# Sheet1.net
KiCad netlist of a schematic drawn in Altium Designer
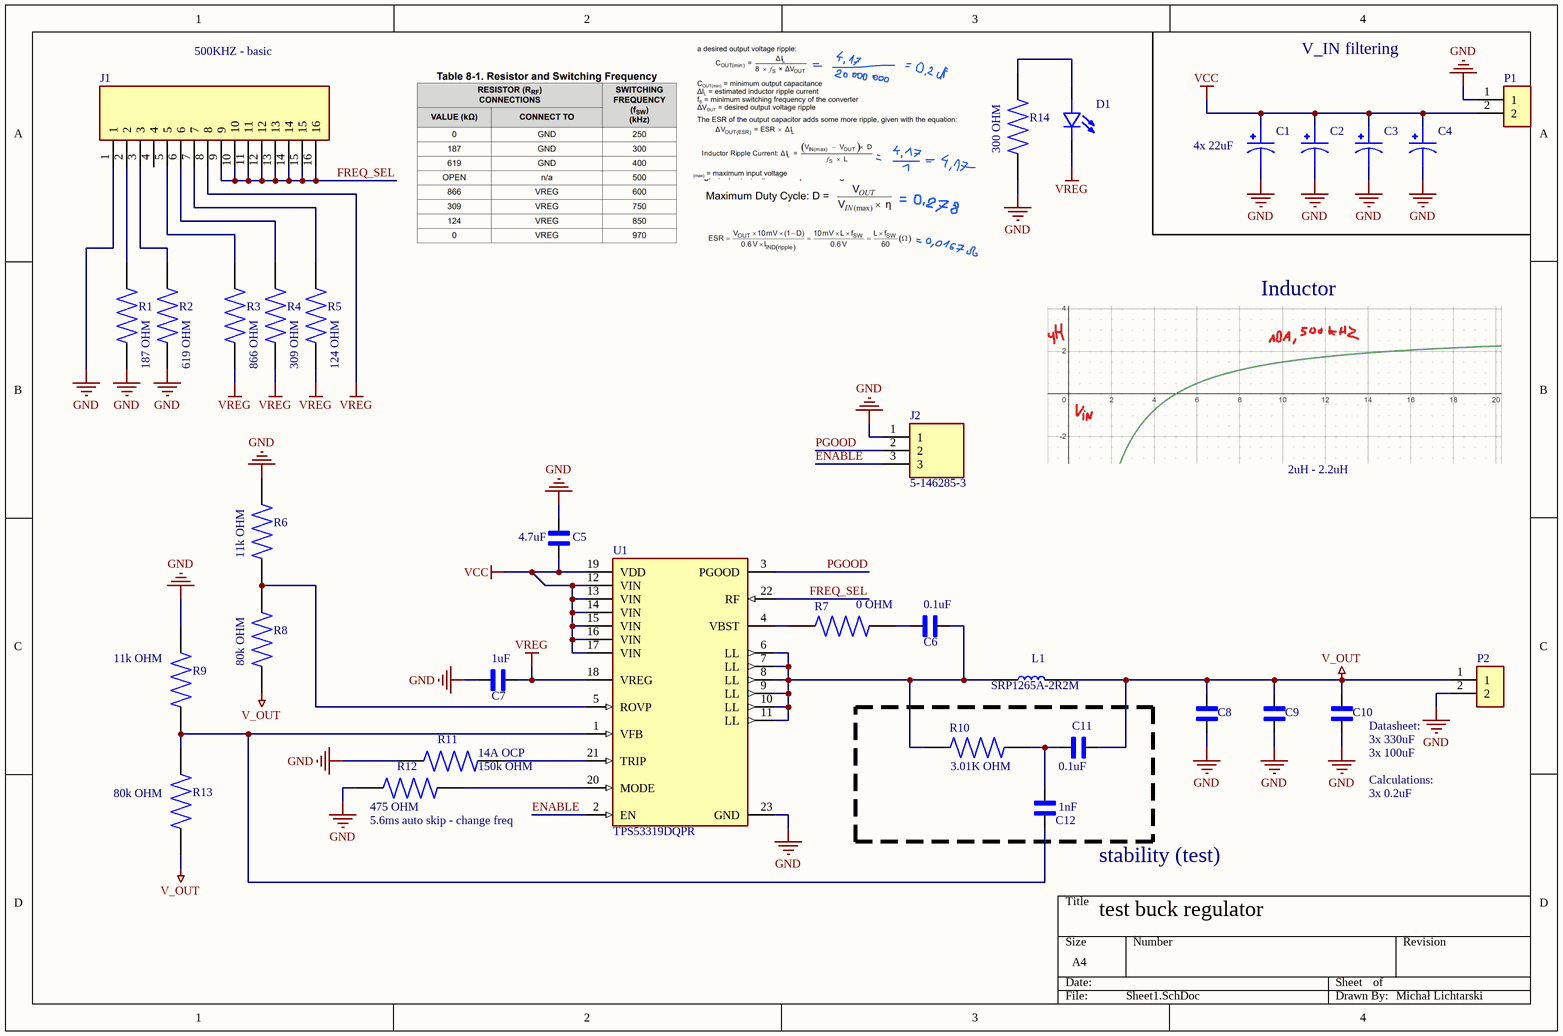
[diagram p0: Sheet1.SchDoc]

(export (version "E")
  (design (tool "Eeschema 10.0.6"))
  (components
    (comp (ref "C1")
      (value "TCJD226M035R0070")
      (footprint "TPSD107M016S0100:CAPPM7343X310N")
      (description "CAP TANT POLY 22UF 35V 2917")
      (fields (field (name "MF") "{'manufacturer': u'AVX'}") (field (name "MP") "TPSD107M016S0100"))
      (libsource (lib "*") (part "TPSD107M016S0100"))
    )
    (comp (ref "C2")
      (value "TCJD226M035R0070")
      (footprint "TPSD107M016S0100:CAPPM7343X310N")
      (description "CAP TANT POLY 22UF 35V 2917")
      (fields (field (name "MF") "{'manufacturer': u'AVX'}") (field (name "MP") "TPSD107M016S0100"))
      (libsource (lib "*") (part "TPSD107M016S0100"))
    )
    (comp (ref "C3")
      (value "TCJD226M035R0070")
      (footprint "TPSD107M016S0100:CAPPM7343X310N")
      (description "CAP TANT POLY 22UF 35V 2917")
      (fields (field (name "MF") "{'manufacturer': u'AVX'}") (field (name "MP") "TPSD107M016S0100"))
      (libsource (lib "*") (part "TPSD107M016S0100"))
    )
    (comp (ref "C4")
      (value "TCJD226M035R0070")
      (footprint "TPSD107M016S0100:CAPPM7343X310N")
      (description "CAP TANT POLY 22UF 35V 2917")
      (fields (field (name "MF") "{'manufacturer': u'AVX'}") (field (name "MP") "TPSD107M016S0100"))
      (libsource (lib "*") (part "TPSD107M016S0100"))
    )
    (comp (ref "C5")
      (value "CL21A475KLCLQNC")
      (footprint "CL21A475KLCLQNC:CAPC2012X135N")
      (description "MLCC 0805 X5R 4.7uF Â±10% 35V T:0.85mm")
      (fields (field (name "MF") "{'manufacturer': u'Samsung'}"))
      (libsource (lib "*") (part "CL21A475KLCLQNC"))
    )
    (comp (ref "C6")
      (value "CL10B104KB8NNNC")
      (footprint "CL10B104KB8NNNC:CAPC1608X90N")
      (fields (field (name "MF") "{'manufacturer': u'Samsung Electro-Mechanics'}"))
      (libsource (lib "*") (part "CL10B104KB8NNNC"))
    )
    (comp (ref "C7")
      (value "CL21B105KBFNNNE")
      (footprint "CL21B105KBFNNNE:CAPC2012X140N")
      (description "Capacitor: ceramic; MLCC; 1uF; 50V; X7R; Â±10%; SMD; 0805")
      (fields (field (name "MF") "{'manufacturer': u'Samsung Electro-Mechanics'}"))
      (libsource (lib "*") (part "CL21B105KBFNNNE"))
    )
    (comp (ref "C8")
      (value "CL32A107MPVNNNE")
      (footprint "CL32A107MPVNNNE:ANTC3225X280N")
      (description "Cap Ceramic 100uF 10V X5R 20% SMD 1210 85Â°C Embossed T/R")
      (fields (field (name "MF") "{'manufacturer': u'Samsung Electro-Mechanics'}"))
      (libsource (lib "*") (part "CL32A107MPVNNNE"))
    )
    (comp (ref "C9")
      (value "CL32A107MPVNNNE")
      (footprint "CL32A107MPVNNNE:ANTC3225X280N")
      (description "Cap Ceramic 100uF 10V X5R 20% SMD 1210 85Â°C Embossed T/R")
      (fields (field (name "MF") "{'manufacturer': u'Samsung Electro-Mechanics'}"))
      (libsource (lib "*") (part "CL32A107MPVNNNE"))
    )
    (comp (ref "C10")
      (value "CL32A107MPVNNNE")
      (footprint "CL32A107MPVNNNE:ANTC3225X280N")
      (description "Cap Ceramic 100uF 10V X5R 20% SMD 1210 85Â°C Embossed T/R")
      (fields (field (name "MF") "{'manufacturer': u'Samsung Electro-Mechanics'}"))
      (libsource (lib "*") (part "CL32A107MPVNNNE"))
    )
    (comp (ref "C11")
      (value "CL10B104KB8NNNC")
      (footprint "CL10B104KB8NNNC:CAPC1608X90N")
      (fields (field (name "MF") "{'manufacturer': u'Samsung Electro-Mechanics'}"))
      (libsource (lib "*") (part "CL10B104KB8NNNC"))
    )
    (comp (ref "C12")
      (value "CL10C102JB8NNNC")
      (footprint "CL10B104KB8NNNC:CAPC1608X90N")
      (description "CAP CER 1000PF 50V C0G/NP0 0603")
      (fields
        (field (name "MF") "{'manufacturer': u'Samsung Electro-Mechanics'}")
        (field (name "MP") "CL10B104KB8NNNC")
      )
      (libsource (lib "") (part "CL10B104KB8NNNC_1"))
    )
    (comp (ref "D1")
      (value "LTST-C190GKT")
      (footprint "LTST-C190GKT:LEDC1608X35N")
      (fields (field (name "MF") "{'manufacturer': u'Lite-On Inc.'}"))
      (libsource (lib "*") (part "LTST-C190GKT"))
    )
    (comp (ref "J1")
      (value "87227-8")
      (footprint "87227-8:TE_87227-8")
      (fields (field (name "MF") "{'manufacturer': u'TE Connectivity'}"))
      (libsource (lib "*") (part "87227-8"))
    )
    (comp (ref "J2")
      (value "5-146285-3")
      (footprint "TE_5-146285-3")
      (fields (field (name "MF") "{'manufacturer': u'TE Connectivity'}"))
      (libsource (lib "5-146285-3") (part "5-146285-3"))
    )
    (comp (ref "L1")
      (value "SRP1265A-2R2M")
      (footprint "SRP1265A-330M:IND_SRP1265A-330M")
      (description "Inductor Power Shielded Wirewound 33uH 20% 100KHz Carbonyl Powder 8A 58mOhm DCR Automotive T/R")
      (fields (field (name "MF") "{'manufacturer': u'Bourns'}") (field (name "MP") "SRP1265A-330M"))
      (libsource (lib "*") (part "SRP1265A-330M"))
    )
    (comp (ref "P1")
      (value "282837-2")
      (footprint "282837-2:TE_282837-2")
      (description "TERM BLOCK 5.08MM 2POS SIDE ENTY")
      (fields (field (name "MF") "{'manufacturer': u'TE Connectivity'}"))
      (libsource (lib "*") (part "282837-2"))
    )
    (comp (ref "P2")
      (value "282837-2")
      (footprint "282837-2:TE_282837-2")
      (description "TERM BLOCK 5.08MM 2POS SIDE ENTY")
      (fields (field (name "MF") "{'manufacturer': u'TE Connectivity'}"))
      (libsource (lib "*") (part "282837-2"))
    )
    (comp (ref "R1")
      (value "RC0603FR-07187RL")
      (footprint "ERJ-3EKF4750V:RES_ERJ3EKF4750V")
      (description "RES 187 OHM 1% 1/10W 0603")
      (fields (field (name "MF") "{'manufacturer': u'Panasonic'}") (field (name "MP") "ERJ3EKF4750V"))
      (libsource (lib "*") (part "ERJ3EKF4750V"))
    )
    (comp (ref "R2")
      (value "RC0603FR-07619RL")
      (footprint "ERJ-3EKF4750V:RES_ERJ3EKF4750V")
      (description "RES 619 OHM 1% 1/10W 0603")
      (fields (field (name "MF") "{'manufacturer': u'Panasonic'}") (field (name "MP") "ERJ3EKF4750V"))
      (libsource (lib "*") (part "ERJ3EKF4750V"))
    )
    (comp (ref "R3")
      (value "RC0603FR-07866RL")
      (footprint "ERJ-3EKF4750V:RES_ERJ3EKF4750V")
      (description "RES 866 OHM 1% 1/10W 0603")
      (fields (field (name "MF") "{'manufacturer': u'Panasonic'}") (field (name "MP") "ERJ3EKF4750V"))
      (libsource (lib "*") (part "ERJ3EKF4750V"))
    )
    (comp (ref "R4")
      (value "RC0603FR-07309RL")
      (footprint "ERJ-3EKF4750V:RES_ERJ3EKF4750V")
      (description "RES 309 OHM 1% 1/10W 0603")
      (fields (field (name "MF") "{'manufacturer': u'Panasonic'}") (field (name "MP") "ERJ3EKF4750V"))
      (libsource (lib "*") (part "ERJ3EKF4750V"))
    )
    (comp (ref "R5")
      (value "ERJ-3EKF1240V")
      (footprint "ERJ-3EKF4750V:RES_ERJ3EKF4750V")
      (description "RES SMD 124 OHM 1% 1/10W 0603")
      (fields (field (name "MF") "{'manufacturer': u'Panasonic'}") (field (name "MP") "ERJ3EKF4750V"))
      (libsource (lib "*") (part "ERJ3EKF4750V"))
    )
    (comp (ref "R6")
      (value "ERJ-PB3D1102V")
      (footprint "ERJ-3EKF4750V:RES_ERJ3EKF4750V")
      (description "RES SMD 11K OHM 0.5% 1/5W 0603")
      (fields (field (name "MF") "{'manufacturer': u'Panasonic'}") (field (name "MP") "ERJ3EKF4750V"))
      (libsource (lib "*") (part "ERJ3EKF4750V"))
    )
    (comp (ref "R7")
      (value "ERJ-3GEY0R00V")
      (footprint "ERJ-3GEY0R00V:RES_ERJ-3GEY0R00V")
      (fields (field (name "MF") "{'manufacturer': u'Panasonic'}"))
      (libsource (lib "*") (part "ERJ-3GEY0R00V"))
    )
    (comp (ref "R8")
      (value "RC0603FR-0780K6L")
      (footprint "ERJ-3EKF4750V:RES_ERJ3EKF4750V")
      (description "RES 80.6K OHM 1% 1/10W 0603")
      (fields (field (name "MF") "{'manufacturer': u'Panasonic'}") (field (name "MP") "ERJ3EKF4750V"))
      (libsource (lib "*") (part "ERJ3EKF4750V"))
    )
    (comp (ref "R9")
      (value "ERJ-PB3D1102V")
      (footprint "ERJ-3EKF4750V:RES_ERJ3EKF4750V")
      (description "RES SMD 11K OHM 0.5% 1/5W 0603")
      (fields (field (name "MF") "{'manufacturer': u'Panasonic'}") (field (name "MP") "ERJ3EKF4750V"))
      (libsource (lib "*") (part "ERJ3EKF4750V"))
    )
    (comp (ref "R10")
      (value "ERJ-3EKF3011V")
      (footprint "ERJ-3GEY0R00V:RES_ERJ-3GEY0R00V")
      (description "RES SMD 3.01K OHM 1% 1/10W 0603")
      (fields (field (name "MF") "{'manufacturer': u'Panasonic'}") (field (name "MP") "ERJ-3GEY0R00V"))
      (libsource (lib "*") (part "ERJ-3GEY0R00V"))
    )
    (comp (ref "R11")
      (value "RC0603FR-07150KL")
      (footprint "ERJ-3EKF4750V:RES_ERJ3EKF4750V")
      (description "RES 150K OHM 1% 1/10W 0603")
      (fields (field (name "MF") "{'manufacturer': u'Panasonic'}") (field (name "MP") "ERJ3EKF4750V"))
      (libsource (lib "*") (part "ERJ3EKF4750V"))
    )
    (comp (ref "R12")
      (value "ERJ-3EKF4750V")
      (footprint "ERJ-3EKF4750V:RES_ERJ3EKF4750V")
      (description "RES SMD 475 OHM 1% 1/10W 0603")
      (fields (field (name "MF") "{'manufacturer': u'Panasonic'}") (field (name "MP") "ERJ3EKF4750V"))
      (libsource (lib "*") (part "ERJ3EKF4750V"))
    )
    (comp (ref "R13")
      (value "RC0603FR-0780K6L")
      (footprint "ERJ-3EKF4750V:RES_ERJ3EKF4750V")
      (description "RES 80.6K OHM 1% 1/10W 0603")
      (fields (field (name "MF") "{'manufacturer': u'Panasonic'}") (field (name "MP") "ERJ3EKF4750V"))
      (libsource (lib "*") (part "ERJ3EKF4750V"))
    )
    (comp (ref "R14")
      (value "ERJ-3GEYJ301V")
      (footprint "ERJ-3EKF4750V:RES_ERJ3EKF4750V")
      (description "RES SMD 300 OHM 5% 1/10W 0603")
      (fields (field (name "MF") "{'manufacturer': u'Panasonic'}") (field (name "MP") "ERJ3EKF4750V"))
      (libsource (lib "*") (part "ERJ3EKF4750V"))
    )
    (comp (ref "U1")
      (value "TPS53319DQPR")
      (footprint "FP-DQP0022A-MFG")
      (description "IC REG BUCK ADJUSTABLE 14A 22SON")
      (libsource (lib "Altium Content Vault") (part "dba826845fdfa018faa42a689150bd3"))
    )
  )
  (nets
    (net (code "1") (name "/ENABLE") (class "Default")
      (node (ref "J2") (pin "3") (pinfunction "3_3") (pintype "passive"))
      (node (ref "U1") (pin "2") (pinfunction "EN_2") (pintype "input"))
    )
    (net (code "2") (name "/FREQ_SEL") (class "Default")
      (node (ref "J1") (pin "10") (pinfunction "10_10") (pintype "passive"))
      (node (ref "J1") (pin "11") (pinfunction "11_11") (pintype "passive"))
      (node (ref "J1") (pin "12") (pinfunction "12_12") (pintype "passive"))
      (node (ref "J1") (pin "13") (pinfunction "13_13") (pintype "passive"))
      (node (ref "J1") (pin "14") (pinfunction "14_14") (pintype "passive"))
      (node (ref "J1") (pin "15") (pinfunction "15_15") (pintype "passive"))
      (node (ref "J1") (pin "16") (pinfunction "16_16") (pintype "passive"))
      (node (ref "J1") (pin "9") (pinfunction "9_9") (pintype "passive"))
      (node (ref "U1") (pin "22") (pinfunction "RF_22") (pintype "input"))
    )
    (net (code "3") (name "/PGOOD") (class "Default")
      (node (ref "J2") (pin "2") (pinfunction "2_2") (pintype "passive"))
      (node (ref "U1") (pin "3") (pinfunction "PGOOD_3") (pintype "open_collector"))
    )
    (net (code "4") (name "GND") (class "Default")
      (node (ref "C1") (pin "2") (pinfunction "2_2") (pintype "passive"))
      (node (ref "C10") (pin "2") (pinfunction "2_2") (pintype "passive"))
      (node (ref "C2") (pin "2") (pinfunction "2_2") (pintype "passive"))
      (node (ref "C3") (pin "2") (pinfunction "2_2") (pintype "passive"))
      (node (ref "C4") (pin "2") (pinfunction "2_2") (pintype "passive"))
      (node (ref "C5") (pin "1") (pinfunction "1_1") (pintype "passive"))
      (node (ref "C7") (pin "1") (pinfunction "1_1") (pintype "passive"))
      (node (ref "C8") (pin "2") (pinfunction "2_2") (pintype "passive"))
      (node (ref "C9") (pin "2") (pinfunction "2_2") (pintype "passive"))
      (node (ref "J1") (pin "1") (pinfunction "1_1") (pintype "passive"))
      (node (ref "J2") (pin "1") (pinfunction "1_1") (pintype "passive"))
      (node (ref "P1") (pin "1") (pinfunction "1_1") (pintype "passive"))
      (node (ref "P2") (pin "2") (pinfunction "2_2") (pintype "passive"))
      (node (ref "R1") (pin "1") (pinfunction "1_1") (pintype "passive"))
      (node (ref "R11") (pin "2") (pinfunction "2_2") (pintype "passive"))
      (node (ref "R12") (pin "1") (pinfunction "1_1") (pintype "passive"))
      (node (ref "R14") (pin "1") (pinfunction "1_1") (pintype "passive"))
      (node (ref "R2") (pin "1") (pinfunction "1_1") (pintype "passive"))
      (node (ref "R6") (pin "2") (pinfunction "2_2") (pintype "passive"))
      (node (ref "R9") (pin "2") (pinfunction "2_2") (pintype "passive"))
      (node (ref "U1") (pin "23") (pinfunction "GND_23") (pintype "power_in"))
    )
    (net (code "5") (name "Net-(C6-Pad1)") (class "Default")
      (node (ref "C6") (pin "1") (pinfunction "1_1") (pintype "passive"))
      (node (ref "L1") (pin "1") (pinfunction "1_1") (pintype "passive"))
      (node (ref "R10") (pin "1") (pinfunction "1_1") (pintype "passive"))
      (node (ref "U1") (pin "10") (pinfunction "LL_10") (pintype "output"))
      (node (ref "U1") (pin "11") (pinfunction "LL_11") (pintype "output"))
      (node (ref "U1") (pin "6") (pinfunction "LL_6") (pintype "output"))
      (node (ref "U1") (pin "7") (pinfunction "LL_7") (pintype "output"))
      (node (ref "U1") (pin "8") (pinfunction "LL_8") (pintype "output"))
      (node (ref "U1") (pin "9") (pinfunction "LL_9") (pintype "output"))
    )
    (net (code "6") (name "Net-(C6-Pad2)") (class "Default")
      (node (ref "C6") (pin "2") (pinfunction "2_2") (pintype "passive"))
      (node (ref "R7") (pin "2") (pinfunction "2_2") (pintype "passive"))
    )
    (net (code "7") (name "Net-(C11-Pad2)") (class "Default")
      (node (ref "C11") (pin "2") (pinfunction "2_2") (pintype "passive"))
      (node (ref "C12") (pin "1") (pinfunction "1_1") (pintype "passive"))
      (node (ref "R10") (pin "2") (pinfunction "2_2") (pintype "passive"))
    )
    (net (code "8") (name "Net-(D1-PadA)") (class "Default")
      (node (ref "D1") (pin "A") (pinfunction "A_A") (pintype "passive"))
      (node (ref "R14") (pin "2") (pinfunction "2_2") (pintype "passive"))
    )
    (net (code "9") (name "Net-(J1-Pad2)") (class "Default")
      (node (ref "J1") (pin "2") (pinfunction "2_2") (pintype "passive"))
      (node (ref "R1") (pin "2") (pinfunction "2_2") (pintype "passive"))
    )
    (net (code "10") (name "Net-(J1-Pad3)") (class "Default")
      (node (ref "J1") (pin "3") (pinfunction "3_3") (pintype "passive"))
      (node (ref "R2") (pin "2") (pinfunction "2_2") (pintype "passive"))
    )
    (net (code "11") (name "Net-(J1-Pad5)") (class "Default")
      (node (ref "J1") (pin "5") (pinfunction "5_5") (pintype "passive"))
      (node (ref "R3") (pin "2") (pinfunction "2_2") (pintype "passive"))
    )
    (net (code "12") (name "Net-(J1-Pad6)") (class "Default")
      (node (ref "J1") (pin "6") (pinfunction "6_6") (pintype "passive"))
      (node (ref "R4") (pin "2") (pinfunction "2_2") (pintype "passive"))
    )
    (net (code "13") (name "Net-(J1-Pad7)") (class "Default")
      (node (ref "J1") (pin "7") (pinfunction "7_7") (pintype "passive"))
      (node (ref "R5") (pin "2") (pinfunction "2_2") (pintype "passive"))
    )
    (net (code "14") (name "Net-(U1-MODE)") (class "Default")
      (node (ref "R12") (pin "2") (pinfunction "2_2") (pintype "passive"))
      (node (ref "U1") (pin "20") (pinfunction "MODE_20") (pintype "input"))
    )
    (net (code "15") (name "Net-(U1-ROVP)") (class "Default")
      (node (ref "R6") (pin "1") (pinfunction "1_1") (pintype "passive"))
      (node (ref "R8") (pin "2") (pinfunction "2_2") (pintype "passive"))
      (node (ref "U1") (pin "5") (pinfunction "ROVP_5") (pintype "input"))
    )
    (net (code "16") (name "Net-(U1-TRIP)") (class "Default")
      (node (ref "R11") (pin "1") (pinfunction "1_1") (pintype "passive"))
      (node (ref "U1") (pin "21") (pinfunction "TRIP_21") (pintype "input"))
    )
    (net (code "17") (name "Net-(U1-VBST)") (class "Default")
      (node (ref "R7") (pin "1") (pinfunction "1_1") (pintype "passive"))
      (node (ref "U1") (pin "4") (pinfunction "VBST_4") (pintype "power_in"))
    )
    (net (code "18") (name "Net-(U1-VFB)") (class "Default")
      (node (ref "C12") (pin "2") (pinfunction "2_2") (pintype "passive"))
      (node (ref "R13") (pin "1") (pinfunction "1_1") (pintype "passive"))
      (node (ref "R9") (pin "1") (pinfunction "1_1") (pintype "passive"))
      (node (ref "U1") (pin "1") (pinfunction "VFB_1") (pintype "input"))
    )
    (net (code "19") (name "VCC") (class "Default")
      (node (ref "C1") (pin "1") (pinfunction "1_1") (pintype "passive"))
      (node (ref "C2") (pin "1") (pinfunction "1_1") (pintype "passive"))
      (node (ref "C3") (pin "1") (pinfunction "1_1") (pintype "passive"))
      (node (ref "C4") (pin "1") (pinfunction "1_1") (pintype "passive"))
      (node (ref "C5") (pin "2") (pinfunction "2_2") (pintype "passive"))
      (node (ref "P1") (pin "2") (pinfunction "2_2") (pintype "passive"))
      (node (ref "U1") (pin "12") (pinfunction "VIN_12") (pintype "power_in"))
      (node (ref "U1") (pin "13") (pinfunction "VIN_13") (pintype "power_in"))
      (node (ref "U1") (pin "14") (pinfunction "VIN_14") (pintype "power_in"))
      (node (ref "U1") (pin "15") (pinfunction "VIN_15") (pintype "power_in"))
      (node (ref "U1") (pin "16") (pinfunction "VIN_16") (pintype "power_in"))
      (node (ref "U1") (pin "17") (pinfunction "VIN_17") (pintype "power_in"))
      (node (ref "U1") (pin "19") (pinfunction "VDD_19") (pintype "power_in"))
    )
    (net (code "20") (name "VREG") (class "Default")
      (node (ref "C7") (pin "2") (pinfunction "2_2") (pintype "passive"))
      (node (ref "D1") (pin "C") (pinfunction "C_C") (pintype "passive"))
      (node (ref "J1") (pin "8") (pinfunction "8_8") (pintype "passive"))
      (node (ref "R3") (pin "1") (pinfunction "1_1") (pintype "passive"))
      (node (ref "R4") (pin "1") (pinfunction "1_1") (pintype "passive"))
      (node (ref "R5") (pin "1") (pinfunction "1_1") (pintype "passive"))
      (node (ref "U1") (pin "18") (pinfunction "VREG_18") (pintype "power_in"))
    )
    (net (code "21") (name "V_OUT") (class "Default")
      (node (ref "C10") (pin "1") (pinfunction "1_1") (pintype "passive"))
      (node (ref "C11") (pin "1") (pinfunction "1_1") (pintype "passive"))
      (node (ref "C8") (pin "1") (pinfunction "1_1") (pintype "passive"))
      (node (ref "C9") (pin "1") (pinfunction "1_1") (pintype "passive"))
      (node (ref "L1") (pin "2") (pinfunction "2_2") (pintype "passive"))
      (node (ref "P2") (pin "1") (pinfunction "1_1") (pintype "passive"))
      (node (ref "R13") (pin "2") (pinfunction "2_2") (pintype "passive"))
      (node (ref "R8") (pin "1") (pinfunction "1_1") (pintype "passive"))
    )
    (net (code "22") (name "unconnected-(J1-Pad4)") (class "Default")
      (node (ref "J1") (pin "4") (pinfunction "4_4") (pintype "passive"))
    )
  )
)
